# Sheet1.net
KiCad netlist of a schematic drawn in Altium Designer
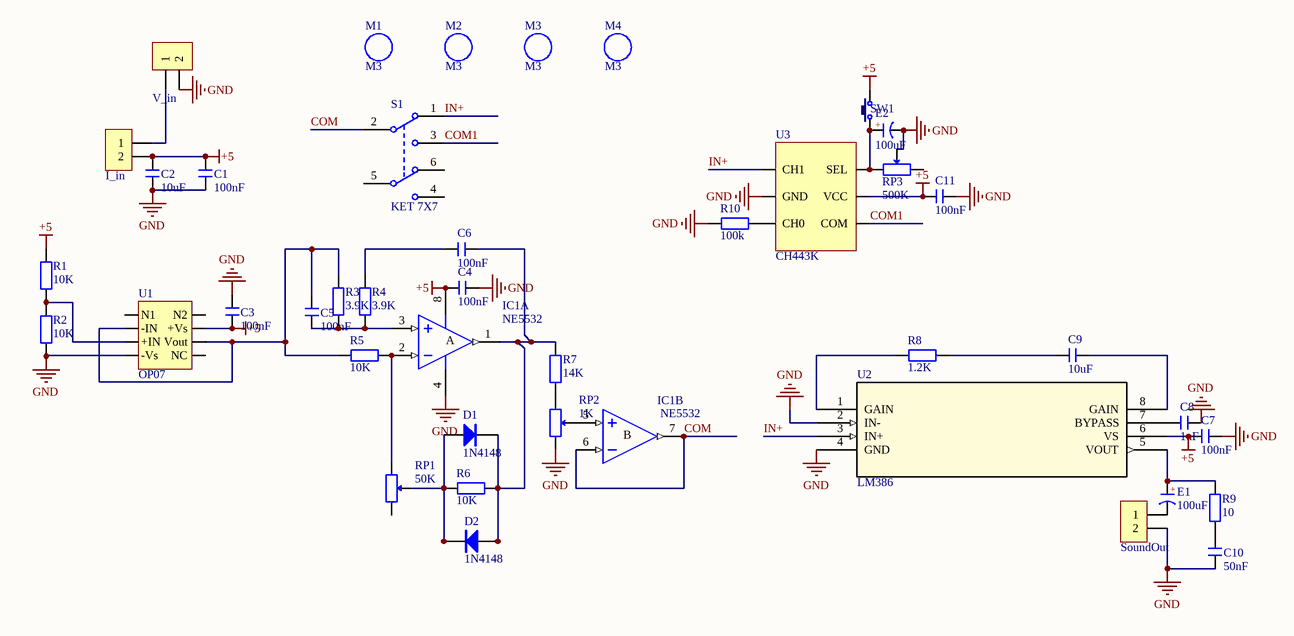
[diagram p0: Sheet1.SchDoc]

(export (version "E")
  (design (tool "Eeschema 10.0.6"))
  (components
    (comp (ref "C1")
      (value "100nF")
      (footprint "C 0603_L")
      (description "无极性贴片电容")
      (fields (field (name "版权归属") "源创客"))
      (libsource (lib "IL") (part "C"))
    )
    (comp (ref "C2")
      (value "10uF")
      (footprint "C 0603_L")
      (description "无极性贴片电容")
      (fields (field (name "版权归属") "源创客"))
      (libsource (lib "IL") (part "C"))
    )
    (comp (ref "C3")
      (value "100nF")
      (footprint "C 0603_L")
      (description "无极性贴片电容")
      (fields (field (name "版权归属") "源创客"))
      (libsource (lib "IL") (part "C"))
    )
    (comp (ref "C4")
      (value "100nF")
      (footprint "C 0603_L")
      (description "无极性贴片电容")
      (fields (field (name "版权归属") "源创客"))
      (libsource (lib "IL") (part "C"))
    )
    (comp (ref "C5")
      (value "100nF")
      (footprint "C 0603_L")
      (description "无极性贴片电容")
      (fields (field (name "版权归属") "源创客"))
      (libsource (lib "IL") (part "C"))
    )
    (comp (ref "C6")
      (value "100nF")
      (footprint "C 0603_L")
      (description "无极性贴片电容")
      (fields (field (name "版权归属") "源创客"))
      (libsource (lib "IL") (part "C"))
    )
    (comp (ref "C7")
      (value "100nF")
      (footprint "C 0603_L")
      (description "无极性贴片电容")
      (fields (field (name "版权归属") "源创客"))
      (libsource (lib "IL") (part "C"))
    )
    (comp (ref "C8")
      (value "1uF")
      (footprint "C 0603_L")
      (description "无极性贴片电容")
      (fields (field (name "版权归属") "源创客"))
      (libsource (lib "IL") (part "C"))
    )
    (comp (ref "C9")
      (value "10uF")
      (footprint "C 0603_L")
      (description "无极性贴片电容")
      (fields (field (name "版权归属") "源创客"))
      (libsource (lib "IL") (part "C"))
    )
    (comp (ref "C10")
      (value "50nF")
      (footprint "C 0603_L")
      (description "无极性贴片电容")
      (fields (field (name "版权归属") "源创客"))
      (libsource (lib "IL") (part "C"))
    )
    (comp (ref "C11")
      (value "100nF")
      (footprint "C 0603_L")
      (description "无极性贴片电容")
      (fields (field (name "版权归属") "源创客"))
      (libsource (lib "IL") (part "C"))
    )
    (comp (ref "D1")
      (value "1N4148")
      (footprint "MINI_MELF (LL34)")
      (description "高速开关二极管")
      (fields (field (name "版权归属") "源创客"))
      (libsource (lib "IL") (part "1N4148"))
    )
    (comp (ref "D2")
      (value "1N4148")
      (footprint "MINI_MELF (LL34)")
      (description "高速开关二极管")
      (fields (field (name "版权归属") "源创客"))
      (libsource (lib "IL") (part "1N4148"))
    )
    (comp (ref "E1")
      (value "100uF")
      (footprint "CAP 2.5*6.3*7")
      (description "直插电解电容")
      (fields (field (name "版权归属") "源创客"))
      (libsource (lib "") (part "C-CAP_1"))
    )
    (comp (ref "E2")
      (value "100uF")
      (footprint "CAP 2.5*6.3*7")
      (description "直插电解电容")
      (fields (field (name "版权归属") "源创客"))
      (libsource (lib "IL") (part "C-CAP"))
    )
    (comp (ref "IC1")
      (value "NE5532")
      (footprint "SOP8_L")
      (description "双路低噪声音频运放")
      (fields (field (name "版权归属") "源创客"))
      (libsource (lib "IL") (part "NE5532"))
    )
    (comp (ref "I_in")
      (value "HDR-1X2")
      (footprint "HDR2.54-LI-2P")
      (description "2P接插件")
      (fields (field (name "版权归属") "源创客"))
      (libsource (lib "") (part "Header 2_1"))
    )
    (comp (ref "M1")
      (value "M3")
      (footprint "M3 125X200")
      (description "铜柱孔")
      (fields (field (name "版权归属") "源创客"))
      (libsource (lib "IL") (part "M3"))
    )
    (comp (ref "M2")
      (value "M3")
      (footprint "M3 125X200")
      (description "铜柱孔")
      (fields (field (name "版权归属") "源创客"))
      (libsource (lib "IL") (part "M3"))
    )
    (comp (ref "M3")
      (value "M3")
      (footprint "M3 125X200")
      (description "铜柱孔")
      (fields (field (name "版权归属") "源创客"))
      (libsource (lib "IL") (part "M3"))
    )
    (comp (ref "M4")
      (value "M3")
      (footprint "M3 125X200")
      (description "铜柱孔")
      (fields (field (name "版权归属") "源创客"))
      (libsource (lib "IL") (part "M3"))
    )
    (comp (ref "R1")
      (value "10K")
      (footprint "R 0603_L")
      (description "贴片电阻")
      (fields (field (name "版权归属") "源创客"))
      (libsource (lib "IL") (part "R"))
    )
    (comp (ref "R2")
      (value "10K")
      (footprint "R 0603_L")
      (description "贴片电阻")
      (fields (field (name "版权归属") "源创客"))
      (libsource (lib "IL") (part "R"))
    )
    (comp (ref "R3")
      (value "3.9K")
      (footprint "R 0603_L")
      (description "贴片电阻")
      (fields (field (name "版权归属") "源创客"))
      (libsource (lib "IL") (part "R"))
    )
    (comp (ref "R4")
      (value "3.9K")
      (footprint "R 0603_L")
      (description "贴片电阻")
      (fields (field (name "版权归属") "源创客"))
      (libsource (lib "IL") (part "R"))
    )
    (comp (ref "R5")
      (value "10K")
      (footprint "R 0603_L")
      (description "贴片电阻")
      (fields (field (name "版权归属") "源创客"))
      (libsource (lib "IL") (part "R"))
    )
    (comp (ref "R6")
      (value "10K")
      (footprint "R 0603_L")
      (description "贴片电阻")
      (fields (field (name "版权归属") "源创客"))
      (libsource (lib "IL") (part "R"))
    )
    (comp (ref "R7")
      (value "14K")
      (footprint "R 0603_L")
      (description "贴片电阻")
      (fields (field (name "版权归属") "源创客"))
      (libsource (lib "IL") (part "R"))
    )
    (comp (ref "R8")
      (value "1.2K")
      (footprint "R 0603_L")
      (description "贴片电阻")
      (fields (field (name "版权归属") "源创客"))
      (libsource (lib "IL") (part "R"))
    )
    (comp (ref "R9")
      (value "10")
      (footprint "R 0603_L")
      (description "贴片电阻")
      (fields (field (name "版权归属") "源创客"))
      (libsource (lib "IL") (part "R"))
    )
    (comp (ref "R10")
      (value "100k")
      (footprint "R 0603_L")
      (description "贴片电阻")
      (fields (field (name "版权归属") "源创客"))
      (libsource (lib "IL") (part "R"))
    )
    (comp (ref "RP1")
      (value "50K")
      (footprint "3296W")
      (description "插件单联电位器")
      (fields (field (name "版权归属") "源创客"))
      (libsource (lib "IL") (part "RP-ID"))
    )
    (comp (ref "RP2")
      (value "1K")
      (footprint "3296W")
      (description "插件单联电位器")
      (fields (field (name "版权归属") "源创客"))
      (libsource (lib "IL") (part "RP-ID"))
    )
    (comp (ref "RP3")
      (value "500K")
      (footprint "3296W")
      (description "插件单联电位器")
      (fields (field (name "版权归属") "源创客"))
      (libsource (lib "IL") (part "RP-ID"))
    )
    (comp (ref "S1")
      (value "KET 7X7")
      (footprint "KFT DIP-7X7")
      (description "7*7自锁开关")
      (fields (field (name "版权归属") "源创客"))
      (libsource (lib "IL") (part "KET 7X7"))
    )
    (comp (ref "SoundOut")
      (value "HDR-1X2")
      (footprint "HDR2.54-LI-2P")
      (description "2P接插件")
      (fields (field (name "版权归属") "源创客"))
      (libsource (lib "") (part "Header 2_1"))
    )
    (comp (ref "SW1")
      (value "3x6x5")
      (footprint "TSW SMD-3*6*2.5")
      (description "3x6轻触开关")
      (fields (field (name "版权归属") "源创客"))
      (libsource (lib "IL") (part "TSW 3x6"))
    )
    (comp (ref "U1")
      (value "OP07")
      (footprint "SOIC-8_L")
      (description "Ultra-Low Offset Voltage Operational Amplifier")
      (fields (field (name "PUBLISHER") "Altium Limited"))
      (libsource (lib "Library") (part "OP07"))
    )
    (comp (ref "U2")
      (value "LM386")
      (footprint "SOP8_L")
      (description "700mW音频功放")
      (fields
        (field (name "MANUFACTURER_PART_NUMBER") "LM386M-1/NOPB")
        (field (name "COPYRIGHT") "Copyright (C) 2021 Ultra Librarian. All rights reserved.")
      )
      (libsource (lib "IL") (part "LM386"))
    )
    (comp (ref "U3")
      (value "CH443K")
      (footprint "SOT65P230X110-6N")
      (libsource (lib "CH443K") (part "CH443K"))
    )
    (comp (ref "V_in")
      (value "HDR-1X2")
      (footprint "HDR2.54-LI-2P")
      (description "2P接插件")
      (fields (field (name "版权归属") "源创客"))
      (libsource (lib "IL") (part "Header 2"))
    )
  )
  (nets
    (net (code "1") (name "+5") (class "Default")
      (node (ref "C1") (pin "2") (pinfunction "2_2") (pintype "passive"))
      (node (ref "C11") (pin "2") (pinfunction "2_2") (pintype "passive"))
      (node (ref "C2") (pin "2") (pinfunction "2_2") (pintype "passive"))
      (node (ref "C3") (pin "1") (pinfunction "1_1") (pintype "passive"))
      (node (ref "C4") (pin "2") (pinfunction "2_2") (pintype "passive"))
      (node (ref "C7") (pin "1") (pinfunction "1_1") (pintype "passive"))
      (node (ref "IC1") (pin "8") (pinfunction "V+_8") (pintype "power_in"))
      (node (ref "I_in") (pin "2") (pinfunction "2_2") (pintype "passive"))
      (node (ref "R1") (pin "2") (pinfunction "2_2") (pintype "passive"))
      (node (ref "SW1") (pin "2") (pinfunction "2_2") (pintype "passive"))
      (node (ref "U1") (pin "7") (pinfunction "+Vs_7") (pintype "passive"))
      (node (ref "U2") (pin "6") (pinfunction "VS_6") (pintype "power_in"))
      (node (ref "U3") (pin "5") (pinfunction "VCC_5") (pintype "passive"))
    )
    (net (code "2") (name "/COM") (class "Default")
      (node (ref "IC1") (pin "6") (pinfunction "IN-_6") (pintype "input"))
      (node (ref "IC1") (pin "7") (pinfunction "OUT_7") (pintype "output"))
      (node (ref "S1") (pin "2") (pinfunction "COM2_2") (pintype "passive"))
    )
    (net (code "3") (name "/COM1") (class "Default")
      (node (ref "S1") (pin "3") (pinfunction "NO1_3") (pintype "passive"))
      (node (ref "U3") (pin "4") (pinfunction "COM_4") (pintype "passive"))
    )
    (net (code "4") (name "/IN+") (class "Default")
      (node (ref "S1") (pin "1") (pinfunction "NC1_1") (pintype "passive"))
      (node (ref "U2") (pin "3") (pinfunction "IN+_3") (pintype "input"))
      (node (ref "U3") (pin "1") (pinfunction "CH1_1") (pintype "passive"))
    )
    (net (code "5") (name "GND") (class "Default")
      (node (ref "C1") (pin "1") (pinfunction "1_1") (pintype "passive"))
      (node (ref "C10") (pin "1") (pinfunction "1_1") (pintype "passive"))
      (node (ref "C11") (pin "1") (pinfunction "1_1") (pintype "passive"))
      (node (ref "C2") (pin "1") (pinfunction "1_1") (pintype "passive"))
      (node (ref "C3") (pin "2") (pinfunction "2_2") (pintype "passive"))
      (node (ref "C4") (pin "1") (pinfunction "1_1") (pintype "passive"))
      (node (ref "C7") (pin "2") (pinfunction "2_2") (pintype "passive"))
      (node (ref "C8") (pin "2") (pinfunction "2_2") (pintype "passive"))
      (node (ref "E2") (pin "2") (pinfunction "K_2") (pintype "passive"))
      (node (ref "IC1") (pin "4") (pinfunction "V-_4") (pintype "power_in"))
      (node (ref "R10") (pin "1") (pinfunction "1_1") (pintype "passive"))
      (node (ref "R2") (pin "1") (pinfunction "1_1") (pintype "passive"))
      (node (ref "RP2") (pin "1") (pinfunction "1_1") (pintype "passive"))
      (node (ref "RP3") (pin "2") (pinfunction "2_2") (pintype "passive"))
      (node (ref "SoundOut") (pin "2") (pinfunction "2_2") (pintype "passive"))
      (node (ref "U1") (pin "4") (pinfunction "-Vs_4") (pintype "passive"))
      (node (ref "U2") (pin "2") (pinfunction "IN-_2") (pintype "input"))
      (node (ref "U2") (pin "4") (pinfunction "GND_4") (pintype "power_in"))
      (node (ref "U3") (pin "2") (pinfunction "GND_2") (pintype "passive"))
      (node (ref "V_in") (pin "2") (pinfunction "2_2") (pintype "passive"))
    )
    (net (code "6") (name "Net-(C6-Pad1)") (class "Default")
      (node (ref "C6") (pin "1") (pinfunction "1_1") (pintype "passive"))
      (node (ref "R4") (pin "2") (pinfunction "2_2") (pintype "passive"))
    )
    (net (code "7") (name "Net-(C9-Pad1)") (class "Default")
      (node (ref "C9") (pin "1") (pinfunction "1_1") (pintype "passive"))
      (node (ref "R8") (pin "2") (pinfunction "2_2") (pintype "passive"))
    )
    (net (code "8") (name "Net-(C9-Pad2)") (class "Default")
      (node (ref "C9") (pin "2") (pinfunction "2_2") (pintype "passive"))
      (node (ref "U2") (pin "8") (pinfunction "GAIN_8") (pintype "passive"))
    )
    (net (code "9") (name "Net-(C10-Pad2)") (class "Default")
      (node (ref "C10") (pin "2") (pinfunction "2_2") (pintype "passive"))
      (node (ref "R9") (pin "1") (pinfunction "1_1") (pintype "passive"))
    )
    (net (code "10") (name "Net-(D1-A)") (class "Default")
      (node (ref "D1") (pin "1") (pinfunction "A_1") (pintype "passive"))
      (node (ref "D2") (pin "2") (pinfunction "K_2") (pintype "passive"))
      (node (ref "R6") (pin "2") (pinfunction "2_2") (pintype "passive"))
      (node (ref "RP1") (pin "2") (pinfunction "2_2") (pintype "passive"))
    )
    (net (code "11") (name "Net-(D1-K)") (class "Default")
      (node (ref "C6") (pin "2") (pinfunction "2_2") (pintype "passive"))
      (node (ref "D1") (pin "2") (pinfunction "K_2") (pintype "passive"))
      (node (ref "D2") (pin "1") (pinfunction "A_1") (pintype "passive"))
      (node (ref "IC1") (pin "1") (pinfunction "OUT_1") (pintype "output"))
      (node (ref "R6") (pin "1") (pinfunction "1_1") (pintype "passive"))
      (node (ref "R7") (pin "1") (pinfunction "1_1") (pintype "passive"))
    )
    (net (code "12") (name "Net-(E1-A)") (class "Default")
      (node (ref "E1") (pin "1") (pinfunction "A_1") (pintype "passive"))
      (node (ref "R9") (pin "2") (pinfunction "2_2") (pintype "passive"))
      (node (ref "U2") (pin "5") (pinfunction "VOUT_5") (pintype "output"))
    )
    (net (code "13") (name "Net-(E1-K)") (class "Default")
      (node (ref "E1") (pin "2") (pinfunction "K_2") (pintype "passive"))
      (node (ref "SoundOut") (pin "1") (pinfunction "1_1") (pintype "passive"))
    )
    (net (code "14") (name "Net-(E2-A)") (class "Default")
      (node (ref "E2") (pin "1") (pinfunction "A_1") (pintype "passive"))
      (node (ref "RP3") (pin "1") (pinfunction "1_1") (pintype "passive"))
      (node (ref "SW1") (pin "1") (pinfunction "1_1") (pintype "passive"))
      (node (ref "U3") (pin "6") (pinfunction "SEL_6") (pintype "passive"))
    )
    (net (code "15") (name "Net-(IC1A-IN+)") (class "Default")
      (node (ref "C5") (pin "2") (pinfunction "2_2") (pintype "passive"))
      (node (ref "IC1") (pin "3") (pinfunction "IN+_3") (pintype "input"))
      (node (ref "R3") (pin "1") (pinfunction "1_1") (pintype "passive"))
      (node (ref "R4") (pin "1") (pinfunction "1_1") (pintype "passive"))
    )
    (net (code "16") (name "Net-(IC1A-IN-)") (class "Default")
      (node (ref "IC1") (pin "2") (pinfunction "IN-_2") (pintype "input"))
      (node (ref "R5") (pin "1") (pinfunction "1_1") (pintype "passive"))
      (node (ref "RP1") (pin "1") (pinfunction "1_1") (pintype "passive"))
    )
    (net (code "17") (name "Net-(IC1B-IN+)") (class "Default")
      (node (ref "IC1") (pin "5") (pinfunction "IN+_5") (pintype "input"))
      (node (ref "RP2") (pin "2") (pinfunction "2_2") (pintype "passive"))
    )
    (net (code "18") (name "Net-(I_in-Pad1)") (class "Default")
      (node (ref "I_in") (pin "1") (pinfunction "1_1") (pintype "passive"))
      (node (ref "V_in") (pin "1") (pinfunction "1_1") (pintype "passive"))
    )
    (net (code "19") (name "Net-(R7-Pad2)") (class "Default")
      (node (ref "R7") (pin "2") (pinfunction "2_2") (pintype "passive"))
      (node (ref "RP2") (pin "3") (pinfunction "3_3") (pintype "passive"))
    )
    (net (code "20") (name "Net-(R8-Pad1)") (class "Default")
      (node (ref "R8") (pin "1") (pinfunction "1_1") (pintype "passive"))
      (node (ref "U2") (pin "1") (pinfunction "GAIN_1") (pintype "passive"))
    )
    (net (code "21") (name "Net-(U1-+IN)") (class "Default")
      (node (ref "R1") (pin "1") (pinfunction "1_1") (pintype "passive"))
      (node (ref "R2") (pin "2") (pinfunction "2_2") (pintype "passive"))
      (node (ref "U1") (pin "3") (pinfunction "+IN_3") (pintype "passive"))
    )
    (net (code "22") (name "Net-(U1--IN)") (class "Default")
      (node (ref "C5") (pin "1") (pinfunction "1_1") (pintype "passive"))
      (node (ref "R3") (pin "2") (pinfunction "2_2") (pintype "passive"))
      (node (ref "R5") (pin "2") (pinfunction "2_2") (pintype "passive"))
      (node (ref "U1") (pin "2") (pinfunction "-IN_2") (pintype "passive"))
      (node (ref "U1") (pin "6") (pinfunction "Vout_6") (pintype "passive"))
    )
    (net (code "23") (name "Net-(U2-BYPASS)") (class "Default")
      (node (ref "C8") (pin "1") (pinfunction "1_1") (pintype "passive"))
      (node (ref "U2") (pin "7") (pinfunction "BYPASS_7") (pintype "passive"))
    )
    (net (code "24") (name "Net-(U3-CH0)") (class "Default")
      (node (ref "R10") (pin "2") (pinfunction "2_2") (pintype "passive"))
      (node (ref "U3") (pin "3") (pinfunction "CH0_3") (pintype "passive"))
    )
    (net (code "25") (name "unconnected-(RP1-Pad3)") (class "Default")
      (node (ref "RP1") (pin "3") (pinfunction "3_3") (pintype "passive"))
    )
    (net (code "26") (name "unconnected-(RP3-Pad3)") (class "Default")
      (node (ref "RP3") (pin "3") (pinfunction "3_3") (pintype "passive"))
    )
    (net (code "27") (name "unconnected-(S1-COM2-Pad5)") (class "Default")
      (node (ref "S1") (pin "5") (pinfunction "COM2_5") (pintype "passive"))
    )
    (net (code "28") (name "unconnected-(S1-NC2-Pad6)") (class "Default")
      (node (ref "S1") (pin "6") (pinfunction "NC2_6") (pintype "passive"))
    )
    (net (code "29") (name "unconnected-(S1-NO2-Pad4)") (class "Default")
      (node (ref "S1") (pin "4") (pinfunction "NO2_4") (pintype "passive"))
    )
    (net (code "30") (name "unconnected-(U1-N1-Pad1)") (class "Default")
      (node (ref "U1") (pin "1") (pinfunction "N1_1") (pintype "passive"))
    )
    (net (code "31") (name "unconnected-(U1-N2-Pad8)") (class "Default")
      (node (ref "U1") (pin "8") (pinfunction "N2_8") (pintype "passive"))
    )
    (net (code "32") (name "unconnected-(U1-NC-Pad5)") (class "Default")
      (node (ref "U1") (pin "5") (pinfunction "NC_5") (pintype "passive"))
    )
  )
)
